# ESCON_Module_48.net
KiCad netlist of a schematic drawn in EAGLE
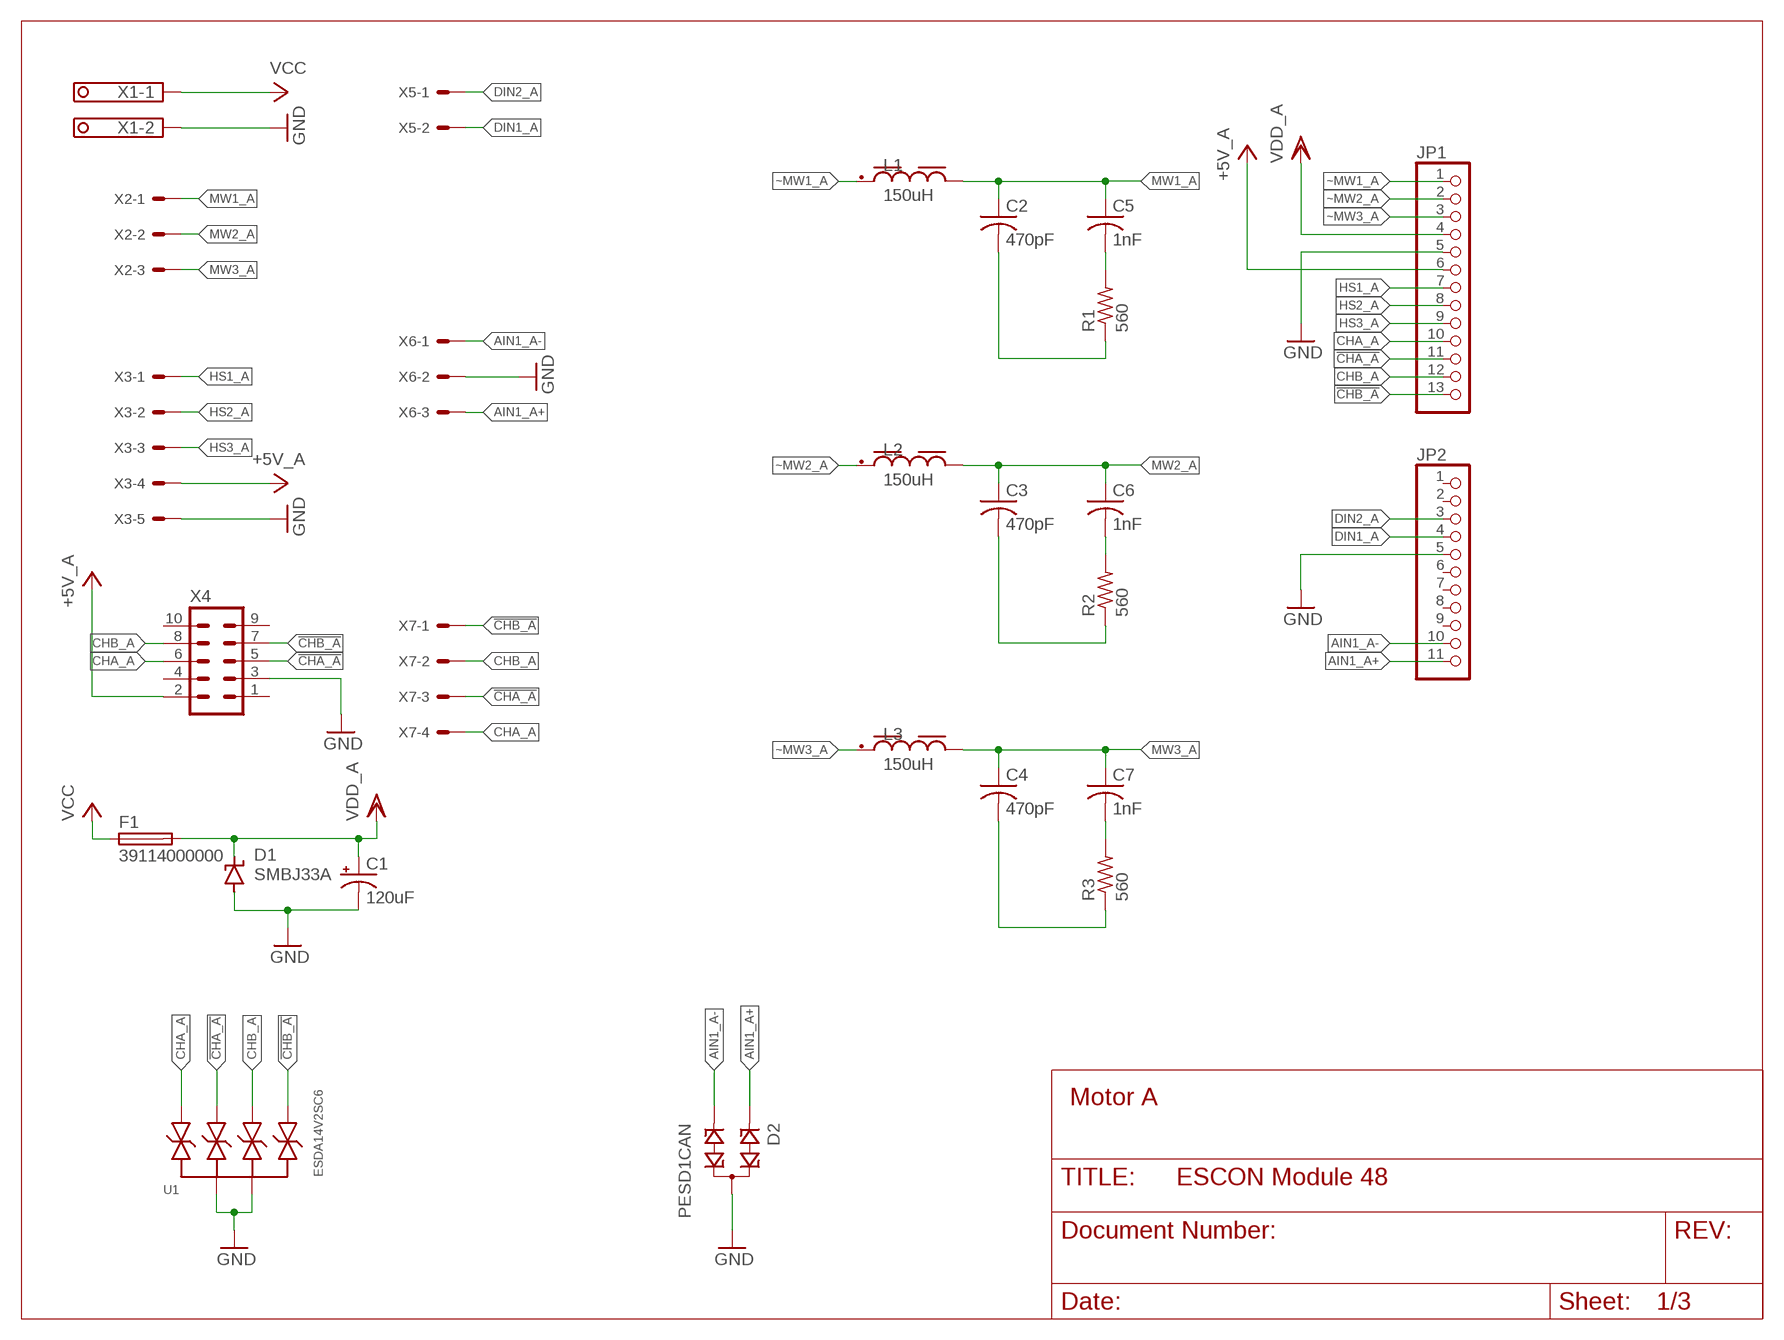
[diagram p0: schematic, sheet 1]
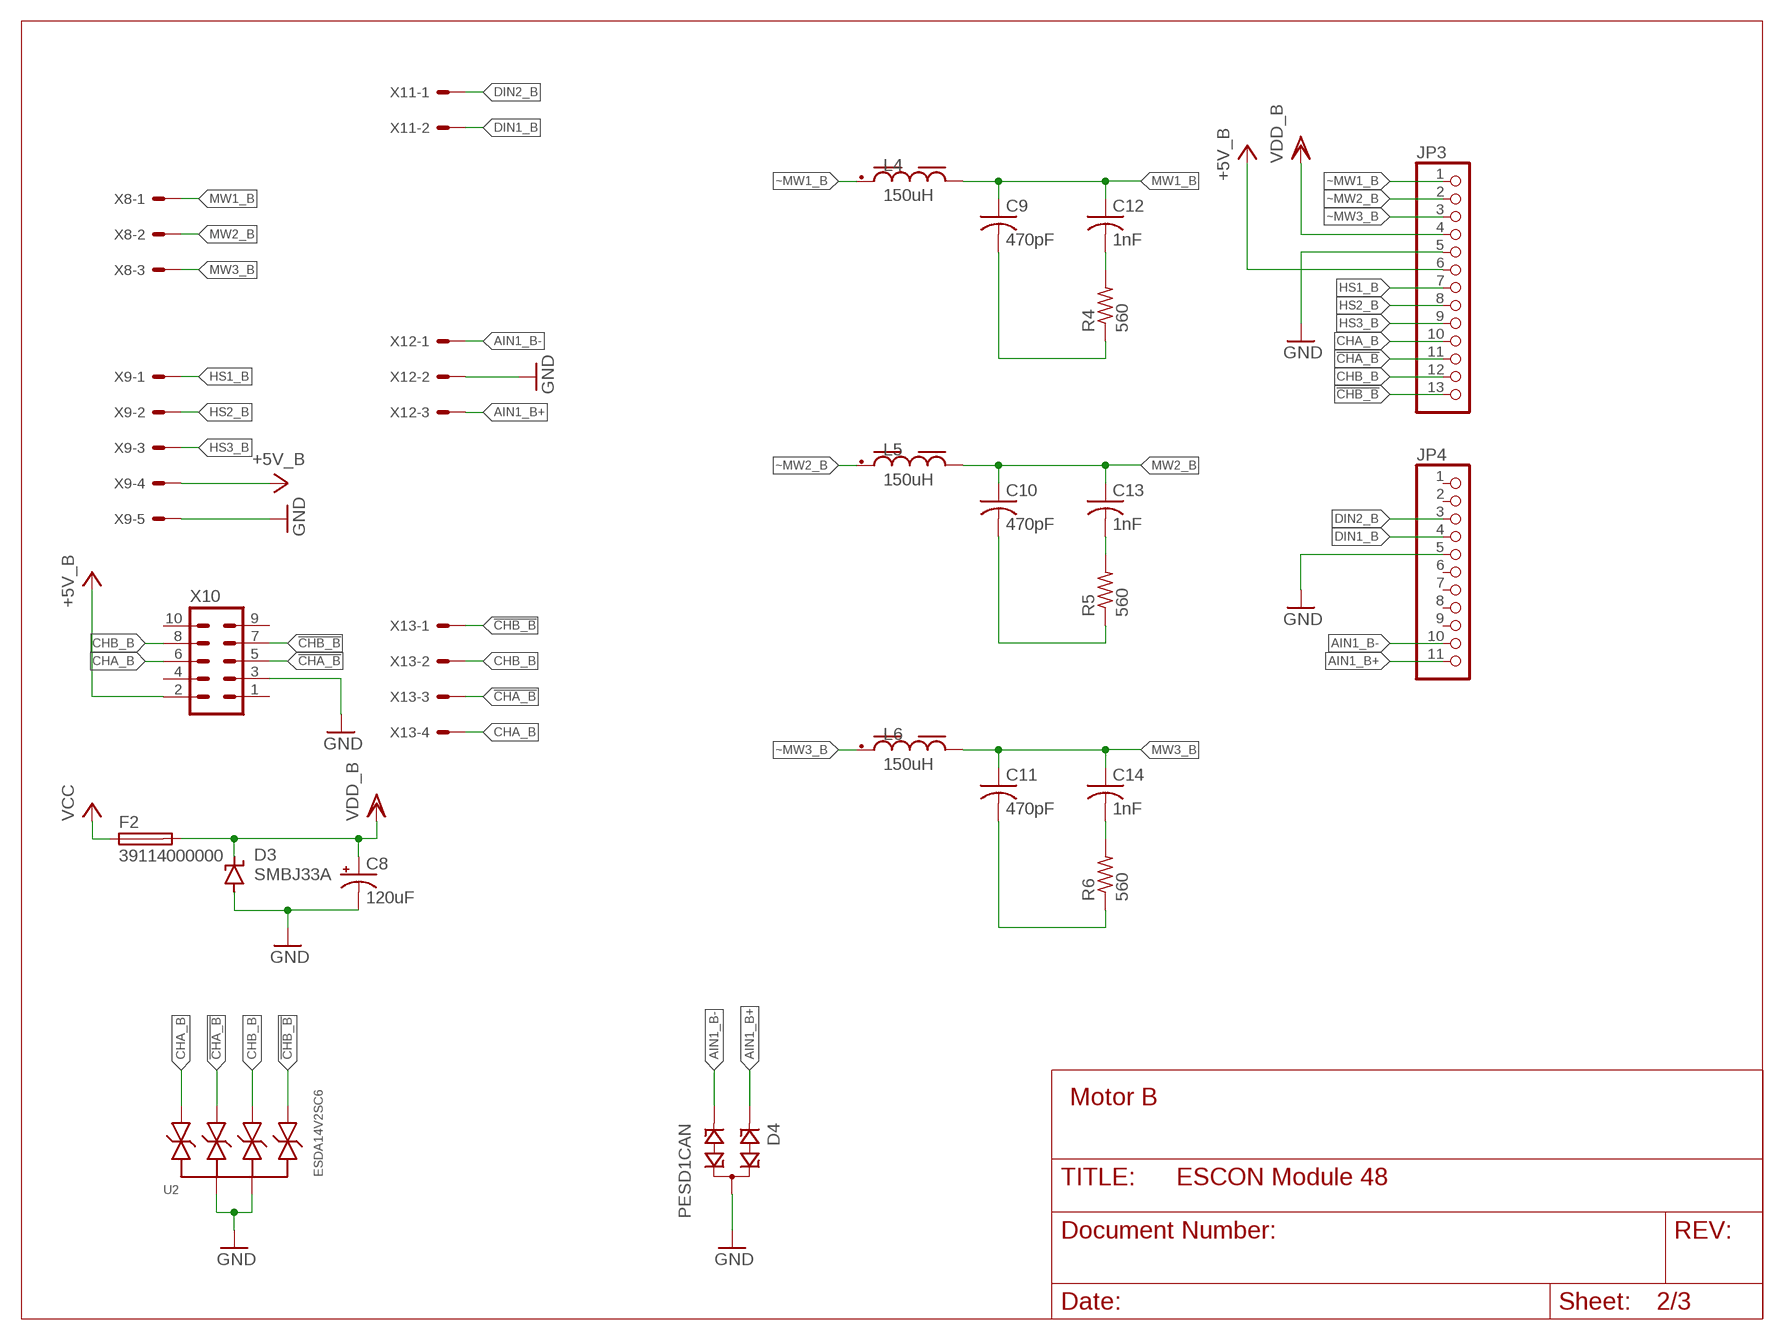
[diagram p1: schematic, sheet 2]
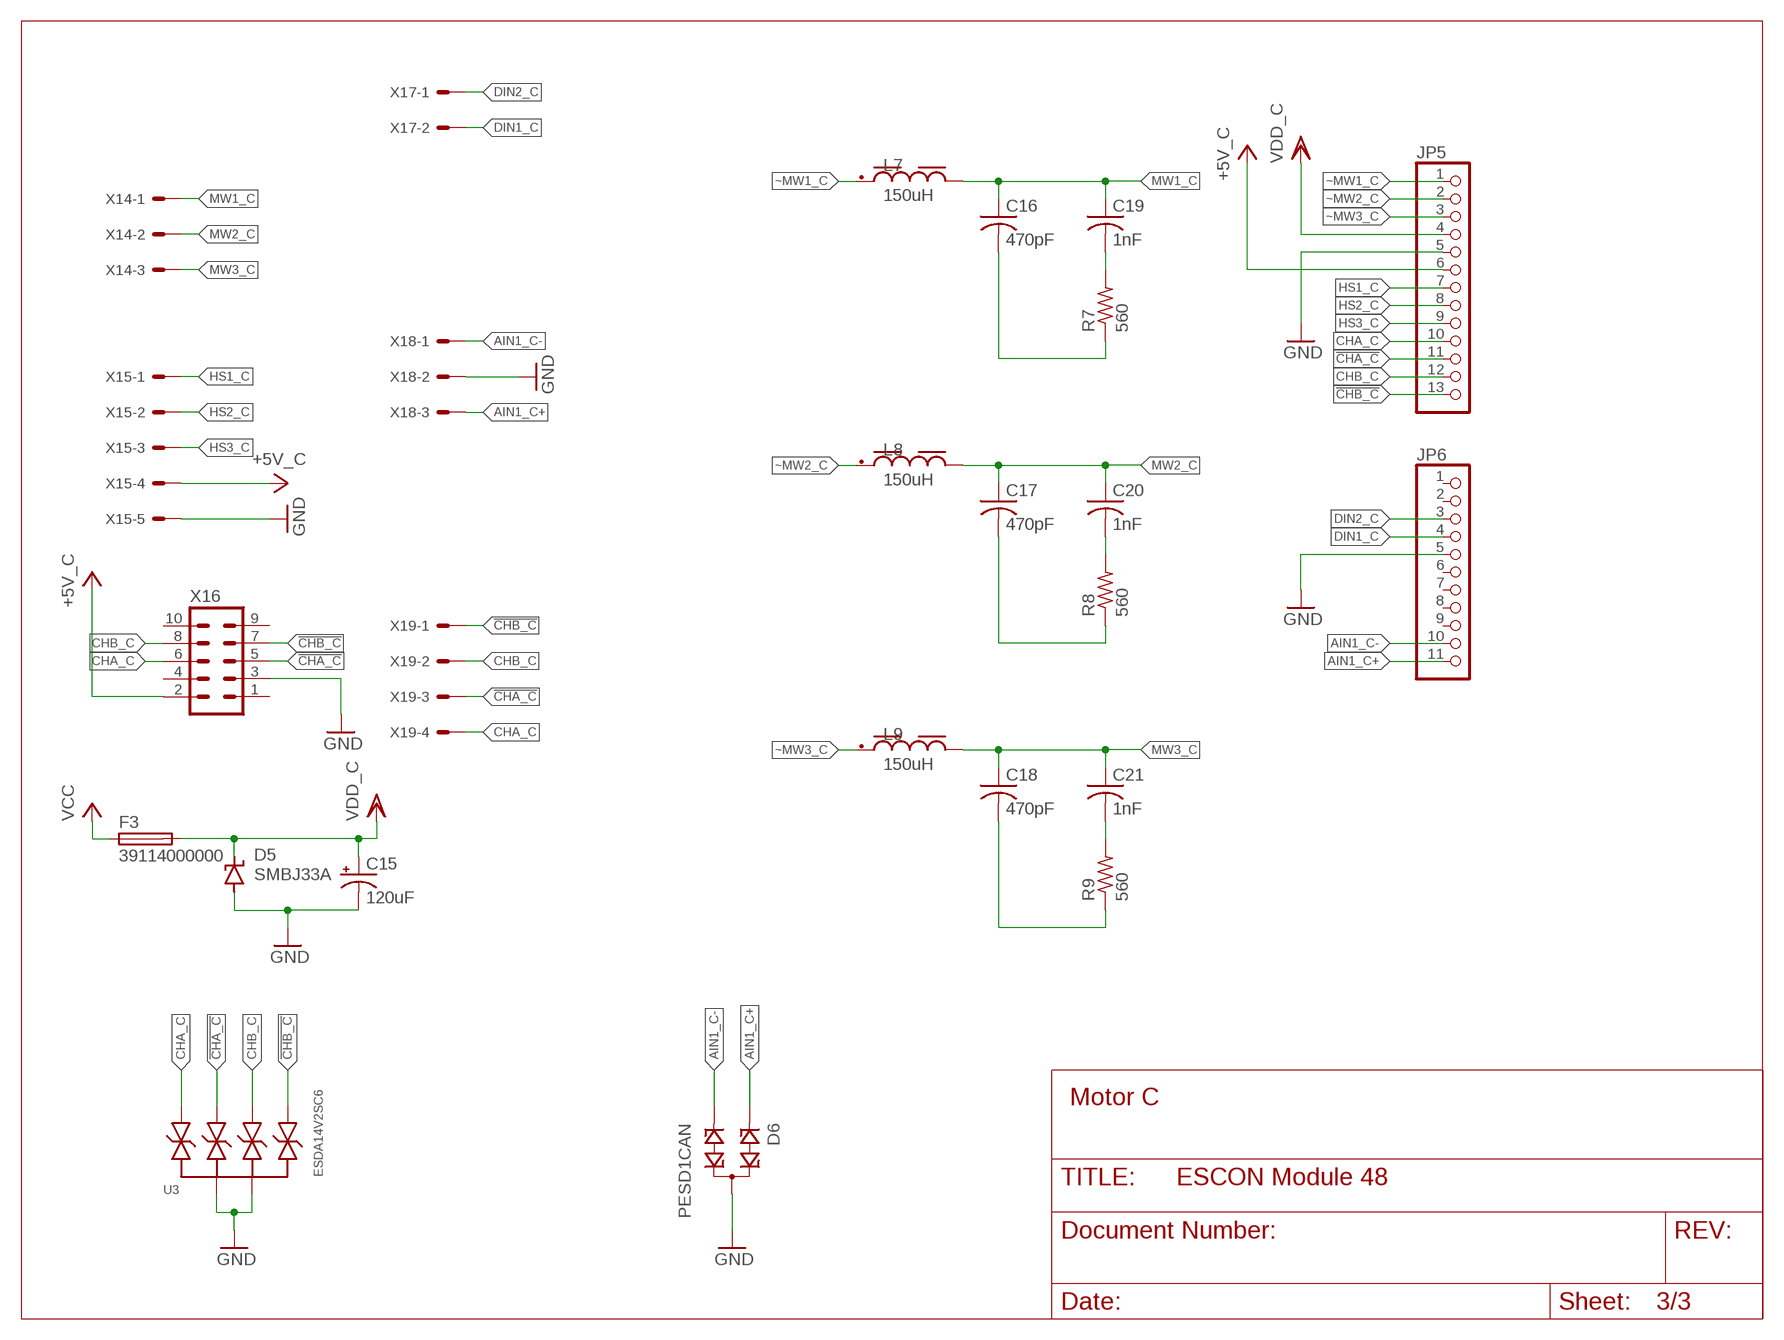
[diagram p2: schematic, sheet 3]

(export (version "E")
  (design (tool "Eeschema 10.0.6"))
  (components
    (comp (ref "C15")
      (value "120uF")
      (footprint "eagle-import:E7,5-16")
      (libsource (lib "eagle-import") (part "CPOL-USE7.5-16"))
    )
    (comp (ref "C16")
      (value "470pF")
      (footprint "eagle-import:C0603")
      (libsource (lib "eagle-import") (part "C-USC0603"))
    )
    (comp (ref "C17")
      (value "470pF")
      (footprint "eagle-import:C0603")
      (libsource (lib "eagle-import") (part "C-USC0603"))
    )
    (comp (ref "C18")
      (value "470pF")
      (footprint "eagle-import:C0603")
      (libsource (lib "eagle-import") (part "C-USC0603"))
    )
    (comp (ref "C19")
      (value "1nF")
      (footprint "eagle-import:C0603")
      (libsource (lib "eagle-import") (part "C-USC0603"))
    )
    (comp (ref "C20")
      (value "1nF")
      (footprint "eagle-import:C0603")
      (libsource (lib "eagle-import") (part "C-USC0603"))
    )
    (comp (ref "C21")
      (value "1nF")
      (footprint "eagle-import:C0603")
      (libsource (lib "eagle-import") (part "C-USC0603"))
    )
    (comp (ref "D5")
      (value "SMBJ33A")
      (footprint "eagle-import:SMBJ")
      (libsource (lib "eagle-import") (part "SUPPRESSOR-SMBJ"))
    )
    (comp (ref "D6")
      (value "PESD1CAN")
      (footprint "eagle-import:SOT23")
      (libsource (lib "eagle-import") (part "PESD1CAN"))
    )
    (comp (ref "F3")
      (value "39114000000")
      (footprint "eagle-import:TE5")
      (libsource (lib "eagle-import") (part "TE5"))
    )
    (comp (ref "JP5")
      (value "PINHD-1X13")
      (footprint "eagle-import:1X13")
      (libsource (lib "eagle-import") (part "PINHD-1X13"))
    )
    (comp (ref "JP6")
      (value "PINHD-1X11")
      (footprint "eagle-import:1X11")
      (libsource (lib "eagle-import") (part "PINHD-1X11"))
    )
    (comp (ref "L7")
      (value "150uH")
      (footprint "eagle-import:WE-PD_1210")
      (libsource (lib "eagle-import") (part "WE-PD_1210_7447709151"))
    )
    (comp (ref "L8")
      (value "150uH")
      (footprint "eagle-import:WE-PD_1210")
      (libsource (lib "eagle-import") (part "WE-PD_1210_7447709151"))
    )
    (comp (ref "L9")
      (value "150uH")
      (footprint "eagle-import:WE-PD_1210")
      (libsource (lib "eagle-import") (part "WE-PD_1210_7447709151"))
    )
    (comp (ref "R7")
      (value "560")
      (footprint "eagle-import:R0603")
      (libsource (lib "eagle-import") (part "R-US_R0603"))
    )
    (comp (ref "R8")
      (value "560")
      (footprint "eagle-import:R0603")
      (libsource (lib "eagle-import") (part "R-US_R0603"))
    )
    (comp (ref "R9")
      (value "560")
      (footprint "eagle-import:R0603")
      (libsource (lib "eagle-import") (part "R-US_R0603"))
    )
    (comp (ref "U3")
      (value "ESDA14V2SC6")
      (footprint "eagle-import:SOT95P280X145-6N")
      (fields (field (name "MF") "STMicroelectronics"))
      (libsource (lib "eagle-import") (part "ESDA14V2SC6"))
    )
    (comp (ref "X14")
      (value "JST-XH-03-PIN-LONG-PAD")
      (footprint "eagle-import:JST-XH-03-PACKAGE-LONG-PAD")
      (libsource (lib "eagle-import") (part "JST-XH-03-PIN-LONG-PAD"))
    )
    (comp (ref "X15")
      (value "JST-XH-05-PIN-LONG-PAD")
      (footprint "eagle-import:JST-XH-05-PACKAGE-LONG-PAD")
      (libsource (lib "eagle-import") (part "JST-XH-05-PIN-LONG-PAD"))
    )
    (comp (ref "X16")
      (value "ML10LP-V")
      (footprint "eagle-import:10LP-V")
      (libsource (lib "eagle-import") (part "ML10LP-V"))
    )
    (comp (ref "X17")
      (value "JST-XH-02-PIN-LONG-PAD")
      (footprint "eagle-import:JST-XH-02-PACKAGE-LONG-PAD")
      (libsource (lib "eagle-import") (part "JST-XH-02-PIN-LONG-PAD"))
    )
    (comp (ref "X18")
      (value "JST-XH-03-PIN-LONG-PAD")
      (footprint "eagle-import:JST-XH-03-PACKAGE-LONG-PAD")
      (libsource (lib "eagle-import") (part "JST-XH-03-PIN-LONG-PAD"))
    )
    (comp (ref "X19")
      (value "JST-XH-04-PIN-LONG-PAD")
      (footprint "eagle-import:JST-XH-04-PACKAGE-LONG-PAD")
      (libsource (lib "eagle-import") (part "JST-XH-04-PIN-LONG-PAD"))
    )
    (comp (ref "C1")
      (value "120uF")
      (footprint "eagle-import:E7,5-16")
      (libsource (lib "eagle-import") (part "CPOL-USE7.5-16"))
    )
    (comp (ref "C2")
      (value "470pF")
      (footprint "eagle-import:C0603")
      (libsource (lib "eagle-import") (part "C-USC0603"))
    )
    (comp (ref "C3")
      (value "470pF")
      (footprint "eagle-import:C0603")
      (libsource (lib "eagle-import") (part "C-USC0603"))
    )
    (comp (ref "C4")
      (value "470pF")
      (footprint "eagle-import:C0603")
      (libsource (lib "eagle-import") (part "C-USC0603"))
    )
    (comp (ref "C5")
      (value "1nF")
      (footprint "eagle-import:C0603")
      (libsource (lib "eagle-import") (part "C-USC0603"))
    )
    (comp (ref "C6")
      (value "1nF")
      (footprint "eagle-import:C0603")
      (libsource (lib "eagle-import") (part "C-USC0603"))
    )
    (comp (ref "C7")
      (value "1nF")
      (footprint "eagle-import:C0603")
      (libsource (lib "eagle-import") (part "C-USC0603"))
    )
    (comp (ref "D1")
      (value "SMBJ33A")
      (footprint "eagle-import:SMBJ")
      (libsource (lib "eagle-import") (part "SUPPRESSOR-SMBJ"))
    )
    (comp (ref "D2")
      (value "PESD1CAN")
      (footprint "eagle-import:SOT23")
      (libsource (lib "eagle-import") (part "PESD1CAN"))
    )
    (comp (ref "F1")
      (value "39114000000")
      (footprint "eagle-import:TE5")
      (libsource (lib "eagle-import") (part "TE5"))
    )
    (comp (ref "JP1")
      (value "PINHD-1X13")
      (footprint "eagle-import:1X13")
      (libsource (lib "eagle-import") (part "PINHD-1X13"))
    )
    (comp (ref "JP2")
      (value "PINHD-1X11")
      (footprint "eagle-import:1X11")
      (libsource (lib "eagle-import") (part "PINHD-1X11"))
    )
    (comp (ref "L1")
      (value "150uH")
      (footprint "eagle-import:WE-PD_1210")
      (libsource (lib "eagle-import") (part "WE-PD_1210_7447709151"))
    )
    (comp (ref "L2")
      (value "150uH")
      (footprint "eagle-import:WE-PD_1210")
      (libsource (lib "eagle-import") (part "WE-PD_1210_7447709151"))
    )
    (comp (ref "L3")
      (value "150uH")
      (footprint "eagle-import:WE-PD_1210")
      (libsource (lib "eagle-import") (part "WE-PD_1210_7447709151"))
    )
    (comp (ref "R1")
      (value "560")
      (footprint "eagle-import:R0603")
      (libsource (lib "eagle-import") (part "R-US_R0603"))
    )
    (comp (ref "R2")
      (value "560")
      (footprint "eagle-import:R0603")
      (libsource (lib "eagle-import") (part "R-US_R0603"))
    )
    (comp (ref "R3")
      (value "560")
      (footprint "eagle-import:R0603")
      (libsource (lib "eagle-import") (part "R-US_R0603"))
    )
    (comp (ref "U1")
      (value "ESDA14V2SC6")
      (footprint "eagle-import:SOT95P280X145-6N")
      (fields (field (name "MF") "STMicroelectronics"))
      (libsource (lib "eagle-import") (part "ESDA14V2SC6"))
    )
    (comp (ref "X1")
      (value "TERMINAL-BLOCK-3.5MM-2-PIN-LONG-PAD")
      (footprint "eagle-import:TERMINAL-BLOCK-2-PIN-3.5MM-LONG-PAD")
      (libsource (lib "eagle-import") (part "TERMINAL-BLOCK-3.5MM-2-PIN-LONG-PAD"))
    )
    (comp (ref "X2")
      (value "JST-XH-03-PIN-LONG-PAD")
      (footprint "eagle-import:JST-XH-03-PACKAGE-LONG-PAD")
      (libsource (lib "eagle-import") (part "JST-XH-03-PIN-LONG-PAD"))
    )
    (comp (ref "X3")
      (value "JST-XH-05-PIN-LONG-PAD")
      (footprint "eagle-import:JST-XH-05-PACKAGE-LONG-PAD")
      (libsource (lib "eagle-import") (part "JST-XH-05-PIN-LONG-PAD"))
    )
    (comp (ref "X4")
      (value "ML10LP-V")
      (footprint "eagle-import:10LP-V")
      (libsource (lib "eagle-import") (part "ML10LP-V"))
    )
    (comp (ref "X5")
      (value "JST-XH-02-PIN-LONG-PAD")
      (footprint "eagle-import:JST-XH-02-PACKAGE-LONG-PAD")
      (libsource (lib "eagle-import") (part "JST-XH-02-PIN-LONG-PAD"))
    )
    (comp (ref "X6")
      (value "JST-XH-03-PIN-LONG-PAD")
      (footprint "eagle-import:JST-XH-03-PACKAGE-LONG-PAD")
      (libsource (lib "eagle-import") (part "JST-XH-03-PIN-LONG-PAD"))
    )
    (comp (ref "X7")
      (value "JST-XH-04-PIN-LONG-PAD")
      (footprint "eagle-import:JST-XH-04-PACKAGE-LONG-PAD")
      (libsource (lib "eagle-import") (part "JST-XH-04-PIN-LONG-PAD"))
    )
    (comp (ref "C8")
      (value "120uF")
      (footprint "eagle-import:E7,5-16")
      (libsource (lib "eagle-import") (part "CPOL-USE7.5-16"))
    )
    (comp (ref "C9")
      (value "470pF")
      (footprint "eagle-import:C0603")
      (libsource (lib "eagle-import") (part "C-USC0603"))
    )
    (comp (ref "C10")
      (value "470pF")
      (footprint "eagle-import:C0603")
      (libsource (lib "eagle-import") (part "C-USC0603"))
    )
    (comp (ref "C11")
      (value "470pF")
      (footprint "eagle-import:C0603")
      (libsource (lib "eagle-import") (part "C-USC0603"))
    )
    (comp (ref "C12")
      (value "1nF")
      (footprint "eagle-import:C0603")
      (libsource (lib "eagle-import") (part "C-USC0603"))
    )
    (comp (ref "C13")
      (value "1nF")
      (footprint "eagle-import:C0603")
      (libsource (lib "eagle-import") (part "C-USC0603"))
    )
    (comp (ref "C14")
      (value "1nF")
      (footprint "eagle-import:C0603")
      (libsource (lib "eagle-import") (part "C-USC0603"))
    )
    (comp (ref "D3")
      (value "SMBJ33A")
      (footprint "eagle-import:SMBJ")
      (libsource (lib "eagle-import") (part "SUPPRESSOR-SMBJ"))
    )
    (comp (ref "D4")
      (value "PESD1CAN")
      (footprint "eagle-import:SOT23")
      (libsource (lib "eagle-import") (part "PESD1CAN"))
    )
    (comp (ref "F2")
      (value "39114000000")
      (footprint "eagle-import:TE5")
      (libsource (lib "eagle-import") (part "TE5"))
    )
    (comp (ref "JP3")
      (value "PINHD-1X13")
      (footprint "eagle-import:1X13")
      (libsource (lib "eagle-import") (part "PINHD-1X13"))
    )
    (comp (ref "JP4")
      (value "PINHD-1X11")
      (footprint "eagle-import:1X11")
      (libsource (lib "eagle-import") (part "PINHD-1X11"))
    )
    (comp (ref "L4")
      (value "150uH")
      (footprint "eagle-import:WE-PD_1210")
      (libsource (lib "eagle-import") (part "WE-PD_1210_7447709151"))
    )
    (comp (ref "L5")
      (value "150uH")
      (footprint "eagle-import:WE-PD_1210")
      (libsource (lib "eagle-import") (part "WE-PD_1210_7447709151"))
    )
    (comp (ref "L6")
      (value "150uH")
      (footprint "eagle-import:WE-PD_1210")
      (libsource (lib "eagle-import") (part "WE-PD_1210_7447709151"))
    )
    (comp (ref "R4")
      (value "560")
      (footprint "eagle-import:R0603")
      (libsource (lib "eagle-import") (part "R-US_R0603"))
    )
    (comp (ref "R5")
      (value "560")
      (footprint "eagle-import:R0603")
      (libsource (lib "eagle-import") (part "R-US_R0603"))
    )
    (comp (ref "R6")
      (value "560")
      (footprint "eagle-import:R0603")
      (libsource (lib "eagle-import") (part "R-US_R0603"))
    )
    (comp (ref "U2")
      (value "ESDA14V2SC6")
      (footprint "eagle-import:SOT95P280X145-6N")
      (fields (field (name "MF") "STMicroelectronics"))
      (libsource (lib "eagle-import") (part "ESDA14V2SC6"))
    )
    (comp (ref "X8")
      (value "JST-XH-03-PIN-LONG-PAD")
      (footprint "eagle-import:JST-XH-03-PACKAGE-LONG-PAD")
      (libsource (lib "eagle-import") (part "JST-XH-03-PIN-LONG-PAD"))
    )
    (comp (ref "X9")
      (value "JST-XH-05-PIN-LONG-PAD")
      (footprint "eagle-import:JST-XH-05-PACKAGE-LONG-PAD")
      (libsource (lib "eagle-import") (part "JST-XH-05-PIN-LONG-PAD"))
    )
    (comp (ref "X10")
      (value "ML10LP-V")
      (footprint "eagle-import:10LP-V")
      (libsource (lib "eagle-import") (part "ML10LP-V"))
    )
    (comp (ref "X11")
      (value "JST-XH-02-PIN-LONG-PAD")
      (footprint "eagle-import:JST-XH-02-PACKAGE-LONG-PAD")
      (libsource (lib "eagle-import") (part "JST-XH-02-PIN-LONG-PAD"))
    )
    (comp (ref "X12")
      (value "JST-XH-03-PIN-LONG-PAD")
      (footprint "eagle-import:JST-XH-03-PACKAGE-LONG-PAD")
      (libsource (lib "eagle-import") (part "JST-XH-03-PIN-LONG-PAD"))
    )
    (comp (ref "X13")
      (value "JST-XH-04-PIN-LONG-PAD")
      (footprint "eagle-import:JST-XH-04-PACKAGE-LONG-PAD")
      (libsource (lib "eagle-import") (part "JST-XH-04-PIN-LONG-PAD"))
    )
  )
  (nets
    (net (code "1") (name "+5V_A") (class "Default")
      (node (ref "JP1") (pin "6") (pinfunction "6_6") (pintype "passive"))
      (node (ref "X3") (pin "4") (pinfunction "S_4") (pintype "passive"))
      (node (ref "X4") (pin "2") (pinfunction "2_2") (pintype "bidirectional"))
    )
    (net (code "2") (name "+5V_B") (class "Default")
      (node (ref "JP3") (pin "6") (pinfunction "6_6") (pintype "passive"))
      (node (ref "X10") (pin "2") (pinfunction "2_2") (pintype "bidirectional"))
      (node (ref "X9") (pin "4") (pinfunction "S_4") (pintype "passive"))
    )
    (net (code "3") (name "+5V_C") (class "Default")
      (node (ref "JP5") (pin "6") (pinfunction "6_6") (pintype "passive"))
      (node (ref "X15") (pin "4") (pinfunction "S_4") (pintype "passive"))
      (node (ref "X16") (pin "2") (pinfunction "2_2") (pintype "bidirectional"))
    )
    (net (code "4") (name "AIN1_A+") (class "Default")
      (node (ref "D2") (pin "1") (pinfunction "1_1") (pintype "passive"))
      (node (ref "JP2") (pin "11") (pinfunction "11_11") (pintype "passive"))
      (node (ref "X6") (pin "3") (pinfunction "S_3") (pintype "passive"))
    )
    (net (code "5") (name "AIN1_A-") (class "Default")
      (node (ref "D2") (pin "2") (pinfunction "2_2") (pintype "passive"))
      (node (ref "JP2") (pin "10") (pinfunction "10_10") (pintype "passive"))
      (node (ref "X6") (pin "1") (pinfunction "S_1") (pintype "passive"))
    )
    (net (code "6") (name "AIN1_B+") (class "Default")
      (node (ref "D4") (pin "1") (pinfunction "1_1") (pintype "passive"))
      (node (ref "JP4") (pin "11") (pinfunction "11_11") (pintype "passive"))
      (node (ref "X12") (pin "3") (pinfunction "S_3") (pintype "passive"))
    )
    (net (code "7") (name "AIN1_B-") (class "Default")
      (node (ref "D4") (pin "2") (pinfunction "2_2") (pintype "passive"))
      (node (ref "JP4") (pin "10") (pinfunction "10_10") (pintype "passive"))
      (node (ref "X12") (pin "1") (pinfunction "S_1") (pintype "passive"))
    )
    (net (code "8") (name "AIN1_C+") (class "Default")
      (node (ref "D6") (pin "1") (pinfunction "1_1") (pintype "passive"))
      (node (ref "JP6") (pin "11") (pinfunction "11_11") (pintype "passive"))
      (node (ref "X18") (pin "3") (pinfunction "S_3") (pintype "passive"))
    )
    (net (code "9") (name "AIN1_C-") (class "Default")
      (node (ref "D6") (pin "2") (pinfunction "2_2") (pintype "passive"))
      (node (ref "JP6") (pin "10") (pinfunction "10_10") (pintype "passive"))
      (node (ref "X18") (pin "1") (pinfunction "S_1") (pintype "passive"))
    )
    (net (code "10") (name "CHA_A") (class "Default")
      (node (ref "JP1") (pin "10") (pinfunction "10_10") (pintype "passive"))
      (node (ref "U1") (pin "1") (pinfunction "1_1") (pintype "passive"))
      (node (ref "X4") (pin "6") (pinfunction "6_6") (pintype "bidirectional"))
      (node (ref "X7") (pin "4") (pinfunction "S_4") (pintype "passive"))
    )
    (net (code "11") (name "CHA_B") (class "Default")
      (node (ref "JP3") (pin "10") (pinfunction "10_10") (pintype "passive"))
      (node (ref "U2") (pin "1") (pinfunction "1_1") (pintype "passive"))
      (node (ref "X10") (pin "6") (pinfunction "6_6") (pintype "bidirectional"))
      (node (ref "X13") (pin "4") (pinfunction "S_4") (pintype "passive"))
    )
    (net (code "12") (name "CHA_C") (class "Default")
      (node (ref "JP5") (pin "10") (pinfunction "10_10") (pintype "passive"))
      (node (ref "U3") (pin "1") (pinfunction "1_1") (pintype "passive"))
      (node (ref "X16") (pin "6") (pinfunction "6_6") (pintype "bidirectional"))
      (node (ref "X19") (pin "4") (pinfunction "S_4") (pintype "passive"))
    )
    (net (code "13") (name "CHB_A") (class "Default")
      (node (ref "JP1") (pin "12") (pinfunction "12_12") (pintype "passive"))
      (node (ref "U1") (pin "4") (pinfunction "4_4") (pintype "passive"))
      (node (ref "X4") (pin "8") (pinfunction "8_8") (pintype "bidirectional"))
      (node (ref "X7") (pin "2") (pinfunction "S_2") (pintype "passive"))
    )
    (net (code "14") (name "CHB_B") (class "Default")
      (node (ref "JP3") (pin "12") (pinfunction "12_12") (pintype "passive"))
      (node (ref "U2") (pin "4") (pinfunction "4_4") (pintype "passive"))
      (node (ref "X10") (pin "8") (pinfunction "8_8") (pintype "bidirectional"))
      (node (ref "X13") (pin "2") (pinfunction "S_2") (pintype "passive"))
    )
    (net (code "15") (name "CHB_C") (class "Default")
      (node (ref "JP5") (pin "12") (pinfunction "12_12") (pintype "passive"))
      (node (ref "U3") (pin "4") (pinfunction "4_4") (pintype "passive"))
      (node (ref "X16") (pin "8") (pinfunction "8_8") (pintype "bidirectional"))
      (node (ref "X19") (pin "2") (pinfunction "S_2") (pintype "passive"))
    )
    (net (code "16") (name "DIN1_A") (class "Default")
      (node (ref "JP2") (pin "4") (pinfunction "4_4") (pintype "passive"))
      (node (ref "X5") (pin "2") (pinfunction "S_2") (pintype "passive"))
    )
    (net (code "17") (name "DIN1_B") (class "Default")
      (node (ref "JP4") (pin "4") (pinfunction "4_4") (pintype "passive"))
      (node (ref "X11") (pin "2") (pinfunction "S_2") (pintype "passive"))
    )
    (net (code "18") (name "DIN1_C") (class "Default")
      (node (ref "JP6") (pin "4") (pinfunction "4_4") (pintype "passive"))
      (node (ref "X17") (pin "2") (pinfunction "S_2") (pintype "passive"))
    )
    (net (code "19") (name "DIN2_A") (class "Default")
      (node (ref "JP2") (pin "3") (pinfunction "3_3") (pintype "passive"))
      (node (ref "X5") (pin "1") (pinfunction "S_1") (pintype "passive"))
    )
    (net (code "20") (name "DIN2_B") (class "Default")
      (node (ref "JP4") (pin "3") (pinfunction "3_3") (pintype "passive"))
      (node (ref "X11") (pin "1") (pinfunction "S_1") (pintype "passive"))
    )
    (net (code "21") (name "DIN2_C") (class "Default")
      (node (ref "JP6") (pin "3") (pinfunction "3_3") (pintype "passive"))
      (node (ref "X17") (pin "1") (pinfunction "S_1") (pintype "passive"))
    )
    (net (code "22") (name "GND") (class "Default")
      (node (ref "C1") (pin "-") (pinfunction "-_-") (pintype "passive"))
      (node (ref "C15") (pin "-") (pinfunction "-_-") (pintype "passive"))
      (node (ref "C8") (pin "-") (pinfunction "-_-") (pintype "passive"))
      (node (ref "D1") (pin "A") (pinfunction "A_A") (pintype "passive"))
      (node (ref "D2") (pin "3") (pinfunction "3_3") (pintype "passive"))
      (node (ref "D3") (pin "A") (pinfunction "A_A") (pintype "passive"))
      (node (ref "D4") (pin "3") (pinfunction "3_3") (pintype "passive"))
      (node (ref "D5") (pin "A") (pinfunction "A_A") (pintype "passive"))
      (node (ref "D6") (pin "3") (pinfunction "3_3") (pintype "passive"))
      (node (ref "JP1") (pin "5") (pinfunction "5_5") (pintype "passive"))
      (node (ref "JP2") (pin "5") (pinfunction "5_5") (pintype "passive"))
      (node (ref "JP3") (pin "5") (pinfunction "5_5") (pintype "passive"))
      (node (ref "JP4") (pin "5") (pinfunction "5_5") (pintype "passive"))
      (node (ref "JP5") (pin "5") (pinfunction "5_5") (pintype "passive"))
      (node (ref "JP6") (pin "5") (pinfunction "5_5") (pintype "passive"))
      (node (ref "U1") (pin "2") (pinfunction "2_2") (pintype "passive"))
      (node (ref "U1") (pin "5") (pinfunction "5_5") (pintype "passive"))
      (node (ref "U2") (pin "2") (pinfunction "2_2") (pintype "passive"))
      (node (ref "U2") (pin "5") (pinfunction "5_5") (pintype "passive"))
      (node (ref "U3") (pin "2") (pinfunction "2_2") (pintype "passive"))
      (node (ref "U3") (pin "5") (pinfunction "5_5") (pintype "passive"))
      (node (ref "X1") (pin "2") (pinfunction "K_2") (pintype "passive"))
      (node (ref "X10") (pin "3") (pinfunction "3_3") (pintype "bidirectional"))
      (node (ref "X12") (pin "2") (pinfunction "S_2") (pintype "passive"))
      (node (ref "X15") (pin "5") (pinfunction "S_5") (pintype "passive"))
      (node (ref "X16") (pin "3") (pinfunction "3_3") (pintype "bidirectional"))
      (node (ref "X18") (pin "2") (pinfunction "S_2") (pintype "passive"))
      (node (ref "X3") (pin "5") (pinfunction "S_5") (pintype "passive"))
      (node (ref "X4") (pin "3") (pinfunction "3_3") (pintype "bidirectional"))
      (node (ref "X6") (pin "2") (pinfunction "S_2") (pintype "passive"))
      (node (ref "X9") (pin "5") (pinfunction "S_5") (pintype "passive"))
    )
    (net (code "23") (name "HS1_A") (class "Default")
      (node (ref "JP1") (pin "7") (pinfunction "7_7") (pintype "passive"))
      (node (ref "X3") (pin "1") (pinfunction "S_1") (pintype "passive"))
    )
    (net (code "24") (name "HS1_B") (class "Default")
      (node (ref "JP3") (pin "7") (pinfunction "7_7") (pintype "passive"))
      (node (ref "X9") (pin "1") (pinfunction "S_1") (pintype "passive"))
    )
    (net (code "25") (name "HS1_C") (class "Default")
      (node (ref "JP5") (pin "7") (pinfunction "7_7") (pintype "passive"))
      (node (ref "X15") (pin "1") (pinfunction "S_1") (pintype "passive"))
    )
    (net (code "26") (name "HS2_A") (class "Default")
      (node (ref "JP1") (pin "8") (pinfunction "8_8") (pintype "passive"))
      (node (ref "X3") (pin "2") (pinfunction "S_2") (pintype "passive"))
    )
    (net (code "27") (name "HS2_B") (class "Default")
      (node (ref "JP3") (pin "8") (pinfunction "8_8") (pintype "passive"))
      (node (ref "X9") (pin "2") (pinfunction "S_2") (pintype "passive"))
    )
    (net (code "28") (name "HS2_C") (class "Default")
      (node (ref "JP5") (pin "8") (pinfunction "8_8") (pintype "passive"))
      (node (ref "X15") (pin "2") (pinfunction "S_2") (pintype "passive"))
    )
    (net (code "29") (name "HS3_A") (class "Default")
      (node (ref "JP1") (pin "9") (pinfunction "9_9") (pintype "passive"))
      (node (ref "X3") (pin "3") (pinfunction "S_3") (pintype "passive"))
    )
    (net (code "30") (name "HS3_B") (class "Default")
      (node (ref "JP3") (pin "9") (pinfunction "9_9") (pintype "passive"))
      (node (ref "X9") (pin "3") (pinfunction "S_3") (pintype "passive"))
    )
    (net (code "31") (name "HS3_C") (class "Default")
      (node (ref "JP5") (pin "9") (pinfunction "9_9") (pintype "passive"))
      (node (ref "X15") (pin "3") (pinfunction "S_3") (pintype "passive"))
    )
    (net (code "32") (name "MW1_A") (class "Default")
      (node (ref "C2") (pin "1") (pinfunction "1_1") (pintype "passive"))
      (node (ref "C5") (pin "1") (pinfunction "1_1") (pintype "passive"))
      (node (ref "L1") (pin "2") (pinfunction "2_2") (pintype "passive"))
      (node (ref "X2") (pin "1") (pinfunction "S_1") (pintype "passive"))
    )
    (net (code "33") (name "MW1_B") (class "Default")
      (node (ref "C12") (pin "1") (pinfunction "1_1") (pintype "passive"))
      (node (ref "C9") (pin "1") (pinfunction "1_1") (pintype "passive"))
      (node (ref "L4") (pin "2") (pinfunction "2_2") (pintype "passive"))
      (node (ref "X8") (pin "1") (pinfunction "S_1") (pintype "passive"))
    )
    (net (code "34") (name "MW1_C") (class "Default")
      (node (ref "C16") (pin "1") (pinfunction "1_1") (pintype "passive"))
      (node (ref "C19") (pin "1") (pinfunction "1_1") (pintype "passive"))
      (node (ref "L7") (pin "2") (pinfunction "2_2") (pintype "passive"))
      (node (ref "X14") (pin "1") (pinfunction "S_1") (pintype "passive"))
    )
    (net (code "35") (name "MW2_A") (class "Default")
      (node (ref "C3") (pin "1") (pinfunction "1_1") (pintype "passive"))
      (node (ref "C6") (pin "1") (pinfunction "1_1") (pintype "passive"))
      (node (ref "L2") (pin "2") (pinfunction "2_2") (pintype "passive"))
      (node (ref "X2") (pin "2") (pinfunction "S_2") (pintype "passive"))
    )
    (net (code "36") (name "MW2_B") (class "Default")
      (node (ref "C10") (pin "1") (pinfunction "1_1") (pintype "passive"))
      (node (ref "C13") (pin "1") (pinfunction "1_1") (pintype "passive"))
      (node (ref "L5") (pin "2") (pinfunction "2_2") (pintype "passive"))
      (node (ref "X8") (pin "2") (pinfunction "S_2") (pintype "passive"))
    )
    (net (code "37") (name "MW2_C") (class "Default")
      (node (ref "C17") (pin "1") (pinfunction "1_1") (pintype "passive"))
      (node (ref "C20") (pin "1") (pinfunction "1_1") (pintype "passive"))
      (node (ref "L8") (pin "2") (pinfunction "2_2") (pintype "passive"))
      (node (ref "X14") (pin "2") (pinfunction "S_2") (pintype "passive"))
    )
    (net (code "38") (name "MW3_A") (class "Default")
      (node (ref "C4") (pin "1") (pinfunction "1_1") (pintype "passive"))
      (node (ref "C7") (pin "1") (pinfunction "1_1") (pintype "passive"))
      (node (ref "L3") (pin "2") (pinfunction "2_2") (pintype "passive"))
      (node (ref "X2") (pin "3") (pinfunction "S_3") (pintype "passive"))
    )
    (net (code "39") (name "MW3_B") (class "Default")
      (node (ref "C11") (pin "1") (pinfunction "1_1") (pintype "passive"))
      (node (ref "C14") (pin "1") (pinfunction "1_1") (pintype "passive"))
      (node (ref "L6") (pin "2") (pinfunction "2_2") (pintype "passive"))
      (node (ref "X8") (pin "3") (pinfunction "S_3") (pintype "passive"))
    )
    (net (code "40") (name "MW3_C") (class "Default")
      (node (ref "C18") (pin "1") (pinfunction "1_1") (pintype "passive"))
      (node (ref "C21") (pin "1") (pinfunction "1_1") (pintype "passive"))
      (node (ref "L9") (pin "2") (pinfunction "2_2") (pintype "passive"))
      (node (ref "X14") (pin "3") (pinfunction "S_3") (pintype "passive"))
    )
    (net (code "41") (name "Net-(C2-Pad2)") (class "Default")
      (node (ref "C2") (pin "2") (pinfunction "2_2") (pintype "passive"))
      (node (ref "R1") (pin "1") (pinfunction "1_1") (pintype "passive"))
    )
    (net (code "42") (name "Net-(C3-Pad2)") (class "Default")
      (node (ref "C3") (pin "2") (pinfunction "2_2") (pintype "passive"))
      (node (ref "R2") (pin "1") (pinfunction "1_1") (pintype "passive"))
    )
    (net (code "43") (name "Net-(C4-Pad2)") (class "Default")
      (node (ref "C4") (pin "2") (pinfunction "2_2") (pintype "passive"))
      (node (ref "R3") (pin "1") (pinfunction "1_1") (pintype "passive"))
    )
    (net (code "44") (name "Net-(C5-Pad2)") (class "Default")
      (node (ref "C5") (pin "2") (pinfunction "2_2") (pintype "passive"))
      (node (ref "R1") (pin "2") (pinfunction "2_2") (pintype "passive"))
    )
    (net (code "45") (name "Net-(C6-Pad2)") (class "Default")
      (node (ref "C6") (pin "2") (pinfunction "2_2") (pintype "passive"))
      (node (ref "R2") (pin "2") (pinfunction "2_2") (pintype "passive"))
    )
    (net (code "46") (name "Net-(C7-Pad2)") (class "Default")
      (node (ref "C7") (pin "2") (pinfunction "2_2") (pintype "passive"))
      (node (ref "R3") (pin "2") (pinfunction "2_2") (pintype "passive"))
    )
    (net (code "47") (name "Net-(C9-Pad2)") (class "Default")
      (node (ref "C9") (pin "2") (pinfunction "2_2") (pintype "passive"))
      (node (ref "R4") (pin "1") (pinfunction "1_1") (pintype "passive"))
    )
    (net (code "48") (name "Net-(C10-Pad2)") (class "Default")
      (node (ref "C10") (pin "2") (pinfunction "2_2") (pintype "passive"))
      (node (ref "R5") (pin "1") (pinfunction "1_1") (pintype "passive"))
    )
    (net (code "49") (name "Net-(C11-Pad2)") (class "Default")
      (node (ref "C11") (pin "2") (pinfunction "2_2") (pintype "passive"))
      (node (ref "R6") (pin "1") (pinfunction "1_1") (pintype "passive"))
    )
    (net (code "50") (name "Net-(C12-Pad2)") (class "Default")
      (node (ref "C12") (pin "2") (pinfunction "2_2") (pintype "passive"))
      (node (ref "R4") (pin "2") (pinfunction "2_2") (pintype "passive"))
    )
    (net (code "51") (name "Net-(C13-Pad2)") (class "Default")
      (node (ref "C13") (pin "2") (pinfunction "2_2") (pintype "passive"))
      (node (ref "R5") (pin "2") (pinfunction "2_2") (pintype "passive"))
    )
    (net (code "52") (name "Net-(C14-Pad2)") (class "Default")
      (node (ref "C14") (pin "2") (pinfunction "2_2") (pintype "passive"))
      (node (ref "R6") (pin "2") (pinfunction "2_2") (pintype "passive"))
    )
    (net (code "53") (name "Net-(C16-Pad2)") (class "Default")
      (node (ref "C16") (pin "2") (pinfunction "2_2") (pintype "passive"))
      (node (ref "R7") (pin "1") (pinfunction "1_1") (pintype "passive"))
    )
    (net (code "54") (name "Net-(C17-Pad2)") (class "Default")
      (node (ref "C17") (pin "2") (pinfunction "2_2") (pintype "passive"))
      (node (ref "R8") (pin "1") (pinfunction "1_1") (pintype "passive"))
    )
    (net (code "55") (name "Net-(C18-Pad2)") (class "Default")
      (node (ref "C18") (pin "2") (pinfunction "2_2") (pintype "passive"))
      (node (ref "R9") (pin "1") (pinfunction "1_1") (pintype "passive"))
    )
    (net (code "56") (name "Net-(C19-Pad2)") (class "Default")
      (node (ref "C19") (pin "2") (pinfunction "2_2") (pintype "passive"))
      (node (ref "R7") (pin "2") (pinfunction "2_2") (pintype "passive"))
    )
    (net (code "57") (name "Net-(C20-Pad2)") (class "Default")
      (node (ref "C20") (pin "2") (pinfunction "2_2") (pintype "passive"))
      (node (ref "R8") (pin "2") (pinfunction "2_2") (pintype "passive"))
    )
    (net (code "58") (name "Net-(C21-Pad2)") (class "Default")
      (node (ref "C21") (pin "2") (pinfunction "2_2") (pintype "passive"))
      (node (ref "R9") (pin "2") (pinfunction "2_2") (pintype "passive"))
    )
    (net (code "59") (name "VCC") (class "Default")
      (node (ref "F1") (pin "1") (pinfunction "1_1") (pintype "passive"))
      (node (ref "F2") (pin "1") (pinfunction "1_1") (pintype "passive"))
      (node (ref "F3") (pin "1") (pinfunction "1_1") (pintype "passive"))
      (node (ref "X1") (pin "1") (pinfunction "K_1") (pintype "passive"))
    )
    (net (code "60") (name "VDD_A") (class "Default")
      (node (ref "C1") (pin "+") (pinfunction "+_+") (pintype "passive"))
      (node (ref "D1") (pin "C") (pinfunction "C_C") (pintype "passive"))
      (node (ref "F1") (pin "2") (pinfunction "2_2") (pintype "passive"))
      (node (ref "JP1") (pin "4") (pinfunction "4_4") (pintype "passive"))
    )
    (net (code "61") (name "VDD_B") (class "Default")
      (node (ref "C8") (pin "+") (pinfunction "+_+") (pintype "passive"))
      (node (ref "D3") (pin "C") (pinfunction "C_C") (pintype "passive"))
      (node (ref "F2") (pin "2") (pinfunction "2_2") (pintype "passive"))
      (node (ref "JP3") (pin "4") (pinfunction "4_4") (pintype "passive"))
    )
    (net (code "62") (name "VDD_C") (class "Default")
      (node (ref "C15") (pin "+") (pinfunction "+_+") (pintype "passive"))
      (node (ref "D5") (pin "C") (pinfunction "C_C") (pintype "passive"))
      (node (ref "F3") (pin "2") (pinfunction "2_2") (pintype "passive"))
      (node (ref "JP5") (pin "4") (pinfunction "4_4") (pintype "passive"))
    )
    (net (code "63") (name "unconnected-(JP2-Pad1)") (class "Default")
      (node (ref "JP2") (pin "1") (pinfunction "1_1") (pintype "passive"))
    )
    (net (code "64") (name "unconnected-(JP2-Pad2)") (class "Default")
      (node (ref "JP2") (pin "2") (pinfunction "2_2") (pintype "passive"))
    )
    (net (code "65") (name "unconnected-(JP2-Pad6)") (class "Default")
      (node (ref "JP2") (pin "6") (pinfunction "6_6") (pintype "passive"))
    )
    (net (code "66") (name "unconnected-(JP2-Pad7)") (class "Default")
      (node (ref "JP2") (pin "7") (pinfunction "7_7") (pintype "passive"))
    )
    (net (code "67") (name "unconnected-(JP2-Pad8)") (class "Default")
      (node (ref "JP2") (pin "8") (pinfunction "8_8") (pintype "passive"))
    )
    (net (code "68") (name "unconnected-(JP2-Pad9)") (class "Default")
      (node (ref "JP2") (pin "9") (pinfunction "9_9") (pintype "passive"))
    )
    (net (code "69") (name "unconnected-(JP4-Pad1)") (class "Default")
      (node (ref "JP4") (pin "1") (pinfunction "1_1") (pintype "passive"))
    )
    (net (code "70") (name "unconnected-(JP4-Pad2)") (class "Default")
      (node (ref "JP4") (pin "2") (pinfunction "2_2") (pintype "passive"))
    )
    (net (code "71") (name "unconnected-(JP4-Pad6)") (class "Default")
      (node (ref "JP4") (pin "6") (pinfunction "6_6") (pintype "passive"))
    )
    (net (code "72") (name "unconnected-(JP4-Pad7)") (class "Default")
      (node (ref "JP4") (pin "7") (pinfunction "7_7") (pintype "passive"))
    )
    (net (code "73") (name "unconnected-(JP4-Pad8)") (class "Default")
      (node (ref "JP4") (pin "8") (pinfunction "8_8") (pintype "passive"))
    )
    (net (code "74") (name "unconnected-(JP4-Pad9)") (class "Default")
      (node (ref "JP4") (pin "9") (pinfunction "9_9") (pintype "passive"))
    )
    (net (code "75") (name "unconnected-(JP6-Pad1)") (class "Default")
      (node (ref "JP6") (pin "1") (pinfunction "1_1") (pintype "passive"))
    )
    (net (code "76") (name "unconnected-(JP6-Pad2)") (class "Default")
      (node (ref "JP6") (pin "2") (pinfunction "2_2") (pintype "passive"))
    )
    (net (code "77") (name "unconnected-(JP6-Pad6)") (class "Default")
      (node (ref "JP6") (pin "6") (pinfunction "6_6") (pintype "passive"))
    )
    (net (code "78") (name "unconnected-(JP6-Pad7)") (class "Default")
      (node (ref "JP6") (pin "7") (pinfunction "7_7") (pintype "passive"))
    )
    (net (code "79") (name "unconnected-(JP6-Pad8)") (class "Default")
      (node (ref "JP6") (pin "8") (pinfunction "8_8") (pintype "passive"))
    )
    (net (code "80") (name "unconnected-(JP6-Pad9)") (class "Default")
      (node (ref "JP6") (pin "9") (pinfunction "9_9") (pintype "passive"))
    )
    (net (code "81") (name "unconnected-(X4-Pad1)") (class "Default")
      (node (ref "X4") (pin "1") (pinfunction "1_1") (pintype "bidirectional"))
    )
    (net (code "82") (name "unconnected-(X4-Pad4)") (class "Default")
      (node (ref "X4") (pin "4") (pinfunction "4_4") (pintype "bidirectional"))
    )
    (net (code "83") (name "unconnected-(X4-Pad9)") (class "Default")
      (node (ref "X4") (pin "9") (pinfunction "9_9") (pintype "bidirectional"))
    )
    (net (code "84") (name "unconnected-(X4-Pad10)") (class "Default")
      (node (ref "X4") (pin "10") (pinfunction "10_10") (pintype "bidirectional"))
    )
    (net (code "85") (name "unconnected-(X10-Pad1)") (class "Default")
      (node (ref "X10") (pin "1") (pinfunction "1_1") (pintype "bidirectional"))
    )
    (net (code "86") (name "unconnected-(X10-Pad4)") (class "Default")
      (node (ref "X10") (pin "4") (pinfunction "4_4") (pintype "bidirectional"))
    )
    (net (code "87") (name "unconnected-(X10-Pad9)") (class "Default")
      (node (ref "X10") (pin "9") (pinfunction "9_9") (pintype "bidirectional"))
    )
    (net (code "88") (name "unconnected-(X10-Pad10)") (class "Default")
      (node (ref "X10") (pin "10") (pinfunction "10_10") (pintype "bidirectional"))
    )
    (net (code "89") (name "unconnected-(X16-Pad1)") (class "Default")
      (node (ref "X16") (pin "1") (pinfunction "1_1") (pintype "bidirectional"))
    )
    (net (code "90") (name "unconnected-(X16-Pad4)") (class "Default")
      (node (ref "X16") (pin "4") (pinfunction "4_4") (pintype "bidirectional"))
    )
    (net (code "91") (name "unconnected-(X16-Pad9)") (class "Default")
      (node (ref "X16") (pin "9") (pinfunction "9_9") (pintype "bidirectional"))
    )
    (net (code "92") (name "unconnected-(X16-Pad10)") (class "Default")
      (node (ref "X16") (pin "10") (pinfunction "10_10") (pintype "bidirectional"))
    )
    (net (code "93") (name "~{CHA_A}") (class "Default")
      (node (ref "JP1") (pin "11") (pinfunction "11_11") (pintype "passive"))
      (node (ref "U1") (pin "3") (pinfunction "3_3") (pintype "passive"))
      (node (ref "X4") (pin "5") (pinfunction "5_5") (pintype "bidirectional"))
      (node (ref "X7") (pin "3") (pinfunction "S_3") (pintype "passive"))
    )
    (net (code "94") (name "~{CHA_B}") (class "Default")
      (node (ref "JP3") (pin "11") (pinfunction "11_11") (pintype "passive"))
      (node (ref "U2") (pin "3") (pinfunction "3_3") (pintype "passive"))
      (node (ref "X10") (pin "5") (pinfunction "5_5") (pintype "bidirectional"))
      (node (ref "X13") (pin "3") (pinfunction "S_3") (pintype "passive"))
    )
    (net (code "95") (name "~{CHA_C}") (class "Default")
      (node (ref "JP5") (pin "11") (pinfunction "11_11") (pintype "passive"))
      (node (ref "U3") (pin "3") (pinfunction "3_3") (pintype "passive"))
      (node (ref "X16") (pin "5") (pinfunction "5_5") (pintype "bidirectional"))
      (node (ref "X19") (pin "3") (pinfunction "S_3") (pintype "passive"))
    )
    (net (code "96") (name "~{CHB_A}") (class "Default")
      (node (ref "JP1") (pin "13") (pinfunction "13_13") (pintype "passive"))
      (node (ref "U1") (pin "6") (pinfunction "6_6") (pintype "passive"))
      (node (ref "X4") (pin "7") (pinfunction "7_7") (pintype "bidirectional"))
      (node (ref "X7") (pin "1") (pinfunction "S_1") (pintype "passive"))
    )
    (net (code "97") (name "~{CHB_B}") (class "Default")
      (node (ref "JP3") (pin "13") (pinfunction "13_13") (pintype "passive"))
      (node (ref "U2") (pin "6") (pinfunction "6_6") (pintype "passive"))
      (node (ref "X10") (pin "7") (pinfunction "7_7") (pintype "bidirectional"))
      (node (ref "X13") (pin "1") (pinfunction "S_1") (pintype "passive"))
    )
    (net (code "98") (name "~{CHB_C}") (class "Default")
      (node (ref "JP5") (pin "13") (pinfunction "13_13") (pintype "passive"))
      (node (ref "U3") (pin "6") (pinfunction "6_6") (pintype "passive"))
      (node (ref "X16") (pin "7") (pinfunction "7_7") (pintype "bidirectional"))
      (node (ref "X19") (pin "1") (pinfunction "S_1") (pintype "passive"))
    )
    (net (code "99") (name "~{MW1_A}") (class "Default")
      (node (ref "JP1") (pin "1") (pinfunction "1_1") (pintype "passive"))
      (node (ref "L1") (pin "1") (pinfunction "1_1") (pintype "passive"))
    )
    (net (code "100") (name "~{MW1_B}") (class "Default")
      (node (ref "JP3") (pin "1") (pinfunction "1_1") (pintype "passive"))
      (node (ref "L4") (pin "1") (pinfunction "1_1") (pintype "passive"))
    )
    (net (code "101") (name "~{MW1_C}") (class "Default")
      (node (ref "JP5") (pin "1") (pinfunction "1_1") (pintype "passive"))
      (node (ref "L7") (pin "1") (pinfunction "1_1") (pintype "passive"))
    )
    (net (code "102") (name "~{MW2_A}") (class "Default")
      (node (ref "JP1") (pin "2") (pinfunction "2_2") (pintype "passive"))
      (node (ref "L2") (pin "1") (pinfunction "1_1") (pintype "passive"))
    )
    (net (code "103") (name "~{MW2_B}") (class "Default")
      (node (ref "JP3") (pin "2") (pinfunction "2_2") (pintype "passive"))
      (node (ref "L5") (pin "1") (pinfunction "1_1") (pintype "passive"))
    )
    (net (code "104") (name "~{MW2_C}") (class "Default")
      (node (ref "JP5") (pin "2") (pinfunction "2_2") (pintype "passive"))
      (node (ref "L8") (pin "1") (pinfunction "1_1") (pintype "passive"))
    )
    (net (code "105") (name "~{MW3_A}") (class "Default")
      (node (ref "JP1") (pin "3") (pinfunction "3_3") (pintype "passive"))
      (node (ref "L3") (pin "1") (pinfunction "1_1") (pintype "passive"))
    )
    (net (code "106") (name "~{MW3_B}") (class "Default")
      (node (ref "JP3") (pin "3") (pinfunction "3_3") (pintype "passive"))
      (node (ref "L6") (pin "1") (pinfunction "1_1") (pintype "passive"))
    )
    (net (code "107") (name "~{MW3_C}") (class "Default")
      (node (ref "JP5") (pin "3") (pinfunction "3_3") (pintype "passive"))
      (node (ref "L9") (pin "1") (pinfunction "1_1") (pintype "passive"))
    )
  )
)
